# Panels.net
KiCad netlist of a schematic drawn in Altium Designer
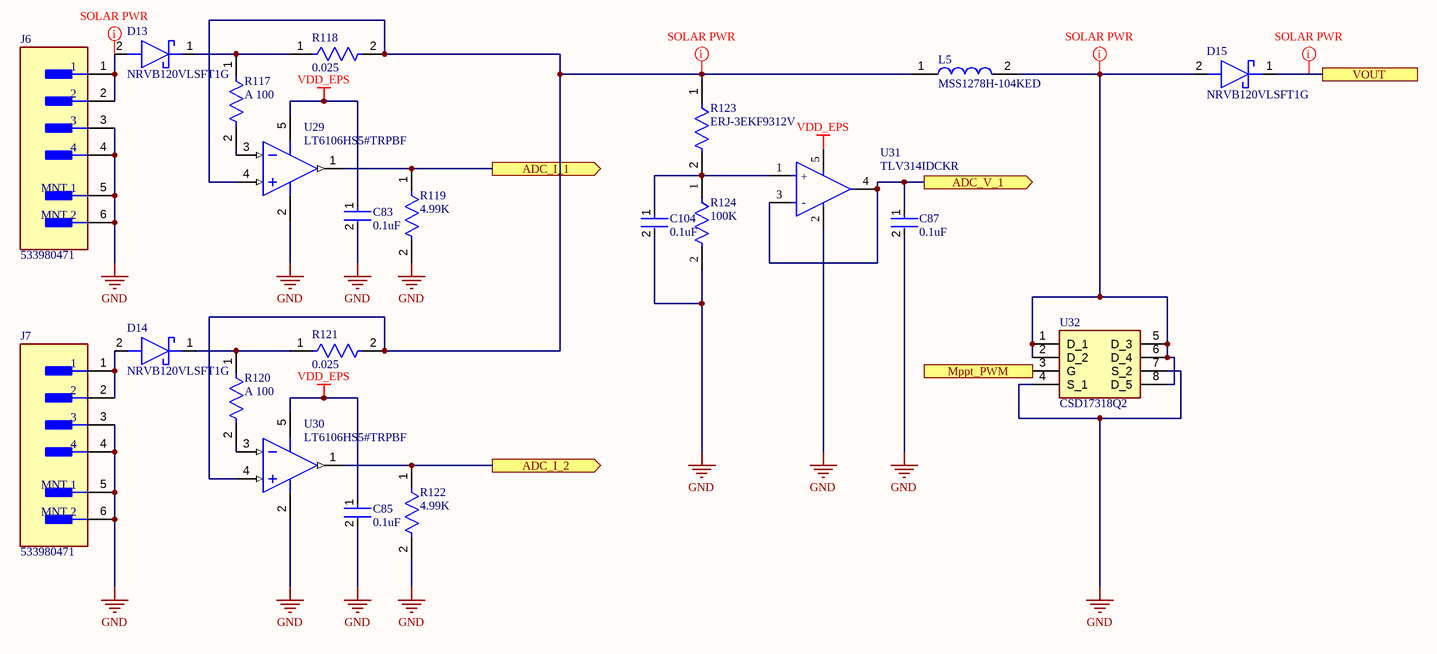
[diagram p0: Panels.SchDoc]

(export (version "E")
  (design (tool "Eeschema 10.0.6"))
  (components
    (comp (ref "C83")
      (value "0.1uF")
      (footprint "FP-C0603C-CF-MFG")
      (description "CAP CER 0.1UF 50V X7R 0603")
      (fields (field (name "TOLERANCE") "0.1") (field (name "MANUFACTURER") "KEMET"))
      (libsource (lib "Altium Content Vault") (part "b4654b650e69147ec39a6b967a45e02"))
    )
    (comp (ref "C85")
      (value "0.1uF")
      (footprint "FP-C0603C-CF-MFG")
      (description "CAP CER 0.1UF 50V X7R 0603")
      (fields (field (name "TOLERANCE") "0.1") (field (name "MANUFACTURER") "KEMET"))
      (libsource (lib "Altium Content Vault") (part "b4654b650e69147ec39a6b967a45e02"))
    )
    (comp (ref "C87")
      (value "0.1uF")
      (footprint "FP-C0603C-CF-MFG")
      (description "CAP CER 0.1UF 50V X7R 0603")
      (fields (field (name "TOLERANCE") "0.1") (field (name "MANUFACTURER") "KEMET"))
      (libsource (lib "Altium Content Vault") (part "b4654b650e69147ec39a6b967a45e02"))
    )
    (comp (ref "C104")
      (value "0.1uF")
      (footprint "FP-C0603C-CF-MFG")
      (description "CAP CER 0.1UF 50V X7R 0603")
      (fields (field (name "TOLERANCE") "0.1") (field (name "MANUFACTURER") "KEMET"))
      (libsource (lib "Altium Content Vault") (part "b4654b650e69147ec39a6b967a45e02"))
    )
    (comp (ref "D13")
      (value "NRVB120VLSFT1G")
      (footprint "SamacSys:SODFL3616X98N")
      (description "Schottky Diode")
      (fields (field (name "MOUSER PART NUMBER") "863-NRVB120VLSFT1G"))
      (libsource (lib "*") (part "NRVB120VLSFT1G"))
    )
    (comp (ref "D14")
      (value "NRVB120VLSFT1G")
      (footprint "SamacSys:SODFL3616X98N")
      (description "Schottky Diode")
      (fields (field (name "MOUSER PART NUMBER") "863-NRVB120VLSFT1G"))
      (libsource (lib "*") (part "NRVB120VLSFT1G"))
    )
    (comp (ref "D15")
      (value "NRVB120VLSFT1G")
      (footprint "SamacSys:SODFL3616X98N")
      (description "Schottky Diode")
      (fields (field (name "MOUSER PART NUMBER") "863-NRVB120VLSFT1G"))
      (libsource (lib "*") (part "NRVB120VLSFT1G"))
    )
    (comp (ref "J6")
      (value "533980471")
      (footprint "FP-533980471-MFG")
      (description "CONN HEADER SMD 4POS 1.25MM")
      (fields
        (field (name "OCTOPART") "https://octopart.com/53398-0471-molex-655296")
        (field (name "MANUFACTURER") "Molex")
      )
      (libsource (lib "Altium Content Vault") (part "3b6f738a5616415d78381ad43816e4a"))
    )
    (comp (ref "J7")
      (value "533980471")
      (footprint "FP-533980471-MFG")
      (description "CONN HEADER SMD 4POS 1.25MM")
      (fields
        (field (name "OCTOPART") "https://octopart.com/53398-0471-molex-655296")
        (field (name "MANUFACTURER") "Molex")
      )
      (libsource (lib "Altium Content Vault") (part "3b6f738a5616415d78381ad43816e4a"))
    )
    (comp (ref "L5")
      (value "MSS1278H-104KED")
      (footprint "INDPM120120X805N")
      (description "Fixed Inductors 100uH Shld 2.3A 10% DCR-121mOhmsAEC-Q200")
      (fields (field (name "MOUSER PART NUMBER") "994-MSS1278H-104KED"))
      (libsource (lib "Hitesh Bhoyar") (part "MSS1278T-104MLD"))
    )
    (comp (ref "R117")
      (value "A 100")
      (footprint "FP-ERA3A-IPC_B")
      (description "RES SMD 100 OHM 0.1% 1/10W 0603")
      (fields (field (name "TOLERANCE") "0.1%"))
      (libsource (lib "Altium Content Vault") (part "1029c3af85768c4190bb7ad29bc67b5"))
    )
    (comp (ref "R118")
      (value "0.025")
      (footprint "FP-PRL0816-MFG")
      (description "25 mOhms ±1% 0.33W Chip Resistor Wide 0306 (0816 Metric), Current Sense Thin Film")
      (fields (field (name "TOLERANCE") "1%"))
      (libsource (lib "Altium Content Vault") (part "1029c3af85768c4190bb7ad29bc67b5"))
    )
    (comp (ref "R119")
      (value "4.99K")
      (footprint "FP-ERA3A-IPC_C")
      (description "RES SMD 4.99KOHM 0.1% 1/10W 0603")
      (fields (field (name "TOLERANCE") "0.1%"))
      (libsource (lib "Altium Content Vault") (part "1029c3af85768c4190bb7ad29bc67b5"))
    )
    (comp (ref "R120")
      (value "A 100")
      (footprint "FP-ERA3A-IPC_B")
      (description "RES SMD 100 OHM 0.1% 1/10W 0603")
      (fields (field (name "TOLERANCE") "0.1%"))
      (libsource (lib "Altium Content Vault") (part "1029c3af85768c4190bb7ad29bc67b5"))
    )
    (comp (ref "R121")
      (value "0.025")
      (footprint "FP-PRL0816-MFG")
      (description "25 mOhms ±1% 0.33W Chip Resistor Wide 0306 (0816 Metric), Current Sense Thin Film")
      (fields (field (name "TOLERANCE") "1%"))
      (libsource (lib "Altium Content Vault") (part "1029c3af85768c4190bb7ad29bc67b5"))
    )
    (comp (ref "R122")
      (value "4.99K")
      (footprint "FP-ERA3A-IPC_C")
      (description "RES SMD 4.99KOHM 0.1% 1/10W 0603")
      (fields (field (name "TOLERANCE") "0.1%"))
      (libsource (lib "Altium Content Vault") (part "1029c3af85768c4190bb7ad29bc67b5"))
    )
    (comp (ref "R123")
      (value "ERJ-3EKF9312V")
      (footprint "FP-ERJ3EK-IPC_C")
      (description "RES SMD 93.1K OHM 1% 1/10W 0603")
      (fields (field (name "TOLERANCE") "1%"))
      (libsource (lib "Altium Content Vault") (part "1029c3af85768c4190bb7ad29bc67b5"))
    )
    (comp (ref "R124")
      (value "100K")
      (footprint "FP-ERA3A-MFG")
      (fields (field (name "TOLERANCE") "0.1%"))
      (libsource (lib "Altium Content Vault") (part "1029c3af85768c4190bb7ad29bc67b5"))
    )
    (comp (ref "U29")
      (value "LT6106HS5#TRPBF")
      (footprint "LT-S5-5-TSOT-23_M")
      (fields
        (field (name "MANUFACTURER") "Linear Technology")
        (field (name "LINEAR TECHNOLOGY PART NUMBER") "LT6106")
      )
      (libsource (lib "Altium Content Vault") (part "LT-LT6106-LTC6101HV-5"))
    )
    (comp (ref "U30")
      (value "LT6106HS5#TRPBF")
      (footprint "LT-S5-5-TSOT-23_M")
      (fields
        (field (name "MANUFACTURER") "Linear Technology")
        (field (name "LINEAR TECHNOLOGY PART NUMBER") "LT6106")
      )
      (libsource (lib "Altium Content Vault") (part "LT-LT6106-LTC6101HV-5"))
    )
    (comp (ref "U31")
      (value "TLV314IDCKR")
      (footprint "FP-DCK0005A-MFG")
      (description "IC CMOS 1 CIRCUIT SC70-5")
      (libsource (lib "Altium Content Vault") (part "000f5c41575af8b8d083a31a5be8140"))
    )
    (comp (ref "U32")
      (value "CSD17318Q2")
      (footprint "SamacSys:CSD17318Q2")
      (description "Integrated Circuit")
      (fields (field (name "MOUSER PART NUMBER") "595-CSD17318Q2"))
      (libsource (lib "*") (part "CSD17318Q2"))
    )
  )
  (nets
    (net (code "1") (name "/ADC_I_1") (class "Default")
      (node (ref "R119") (pin "1") (pinfunction "1_1") (pintype "passive"))
      (node (ref "U29") (pin "1") (pinfunction "OUT_1") (pintype "output"))
    )
    (net (code "2") (name "/ADC_I_2") (class "Default")
      (node (ref "R122") (pin "1") (pinfunction "1_1") (pintype "passive"))
      (node (ref "U30") (pin "1") (pinfunction "OUT_1") (pintype "output"))
    )
    (net (code "3") (name "/ADC_V_1") (class "Default")
      (node (ref "C87") (pin "1") (pinfunction "1_1") (pintype "passive"))
      (node (ref "U31") (pin "3") (pinfunction "-IN_3") (pintype "tri_state"))
      (node (ref "U31") (pin "4") (pinfunction "OUT_4") (pintype "passive"))
    )
    (net (code "4") (name "/Mppt_PWM") (class "Default")
      (node (ref "U32") (pin "3") (pinfunction "G_3") (pintype "passive"))
    )
    (net (code "5") (name "/VOUT") (class "Default")
      (node (ref "D15") (pin "1") (pinfunction "K_1") (pintype "passive"))
    )
    (net (code "6") (name "GND") (class "Default")
      (node (ref "C104") (pin "2") (pinfunction "2_2") (pintype "passive"))
      (node (ref "C83") (pin "2") (pinfunction "2_2") (pintype "passive"))
      (node (ref "C85") (pin "2") (pinfunction "2_2") (pintype "passive"))
      (node (ref "C87") (pin "2") (pinfunction "2_2") (pintype "passive"))
      (node (ref "J6") (pin "3") (pinfunction "3_3") (pintype "passive"))
      (node (ref "J6") (pin "4") (pinfunction "4_4") (pintype "passive"))
      (node (ref "J6") (pin "5") (pinfunction "MNT_1_5") (pintype "passive"))
      (node (ref "J6") (pin "6") (pinfunction "MNT_2_6") (pintype "passive"))
      (node (ref "J7") (pin "3") (pinfunction "3_3") (pintype "passive"))
      (node (ref "J7") (pin "4") (pinfunction "4_4") (pintype "passive"))
      (node (ref "J7") (pin "5") (pinfunction "MNT_1_5") (pintype "passive"))
      (node (ref "J7") (pin "6") (pinfunction "MNT_2_6") (pintype "passive"))
      (node (ref "R119") (pin "2") (pinfunction "2_2") (pintype "passive"))
      (node (ref "R122") (pin "2") (pinfunction "2_2") (pintype "passive"))
      (node (ref "R124") (pin "2") (pinfunction "2_2") (pintype "passive"))
      (node (ref "U29") (pin "2") (pinfunction "V-_2") (pintype "power_in"))
      (node (ref "U30") (pin "2") (pinfunction "V-_2") (pintype "power_in"))
      (node (ref "U31") (pin "2") (pinfunction "V-_2") (pintype "power_in"))
      (node (ref "U32") (pin "4") (pinfunction "S_1_4") (pintype "passive"))
      (node (ref "U32") (pin "7") (pinfunction "S_2_7") (pintype "passive"))
    )
    (net (code "7") (name "Net-(D13-A)") (class "Default")
      (node (ref "D13") (pin "2") (pinfunction "A_2") (pintype "passive"))
      (node (ref "J6") (pin "1") (pinfunction "1_1") (pintype "passive"))
      (node (ref "J6") (pin "2") (pinfunction "2_2") (pintype "passive"))
    )
    (net (code "8") (name "Net-(D13-K)") (class "Default")
      (node (ref "D13") (pin "1") (pinfunction "K_1") (pintype "passive"))
      (node (ref "R117") (pin "1") (pinfunction "1_1") (pintype "passive"))
      (node (ref "R118") (pin "1") (pinfunction "1_1") (pintype "passive"))
    )
    (net (code "9") (name "Net-(D14-A)") (class "Default")
      (node (ref "D14") (pin "2") (pinfunction "A_2") (pintype "passive"))
      (node (ref "J7") (pin "1") (pinfunction "1_1") (pintype "passive"))
      (node (ref "J7") (pin "2") (pinfunction "2_2") (pintype "passive"))
    )
    (net (code "10") (name "Net-(D14-K)") (class "Default")
      (node (ref "D14") (pin "1") (pinfunction "K_1") (pintype "passive"))
      (node (ref "R120") (pin "1") (pinfunction "1_1") (pintype "passive"))
      (node (ref "R121") (pin "1") (pinfunction "1_1") (pintype "passive"))
    )
    (net (code "11") (name "Net-(D15-A)") (class "Default")
      (node (ref "D15") (pin "2") (pinfunction "A_2") (pintype "passive"))
      (node (ref "L5") (pin "2") (pinfunction "2_2") (pintype "passive"))
      (node (ref "U32") (pin "1") (pinfunction "D_1_1") (pintype "passive"))
      (node (ref "U32") (pin "2") (pinfunction "D_2_2") (pintype "passive"))
      (node (ref "U32") (pin "5") (pinfunction "D_3_5") (pintype "passive"))
      (node (ref "U32") (pin "6") (pinfunction "D_4_6") (pintype "passive"))
      (node (ref "U32") (pin "8") (pinfunction "D_5_8") (pintype "passive"))
    )
    (net (code "12") (name "Net-(U29-+IN)") (class "Default")
      (node (ref "L5") (pin "1") (pinfunction "1_1") (pintype "passive"))
      (node (ref "R118") (pin "2") (pinfunction "2_2") (pintype "passive"))
      (node (ref "R121") (pin "2") (pinfunction "2_2") (pintype "passive"))
      (node (ref "R123") (pin "1") (pinfunction "1_1") (pintype "passive"))
      (node (ref "U29") (pin "4") (pinfunction "+IN_4") (pintype "input"))
      (node (ref "U30") (pin "4") (pinfunction "+IN_4") (pintype "input"))
    )
    (net (code "13") (name "Net-(U29--IN)") (class "Default")
      (node (ref "R117") (pin "2") (pinfunction "2_2") (pintype "passive"))
      (node (ref "U29") (pin "3") (pinfunction "-IN_3") (pintype "input"))
    )
    (net (code "14") (name "Net-(U30--IN)") (class "Default")
      (node (ref "R120") (pin "2") (pinfunction "2_2") (pintype "passive"))
      (node (ref "U30") (pin "3") (pinfunction "-IN_3") (pintype "input"))
    )
    (net (code "15") (name "Net-(U31-+IN)") (class "Default")
      (node (ref "C104") (pin "1") (pinfunction "1_1") (pintype "passive"))
      (node (ref "R123") (pin "2") (pinfunction "2_2") (pintype "passive"))
      (node (ref "R124") (pin "1") (pinfunction "1_1") (pintype "passive"))
      (node (ref "U31") (pin "1") (pinfunction "+IN_1") (pintype "tri_state"))
    )
    (net (code "16") (name "VDD_EPS") (class "Default")
      (node (ref "C83") (pin "1") (pinfunction "1_1") (pintype "passive"))
      (node (ref "C85") (pin "1") (pinfunction "1_1") (pintype "passive"))
      (node (ref "U29") (pin "5") (pinfunction "V+_5") (pintype "power_in"))
      (node (ref "U30") (pin "5") (pinfunction "V+_5") (pintype "power_in"))
      (node (ref "U31") (pin "5") (pinfunction "V+_5") (pintype "power_in"))
    )
  )
)
